# LED_Heart.net
KiCad netlist of a schematic drawn in EAGLE
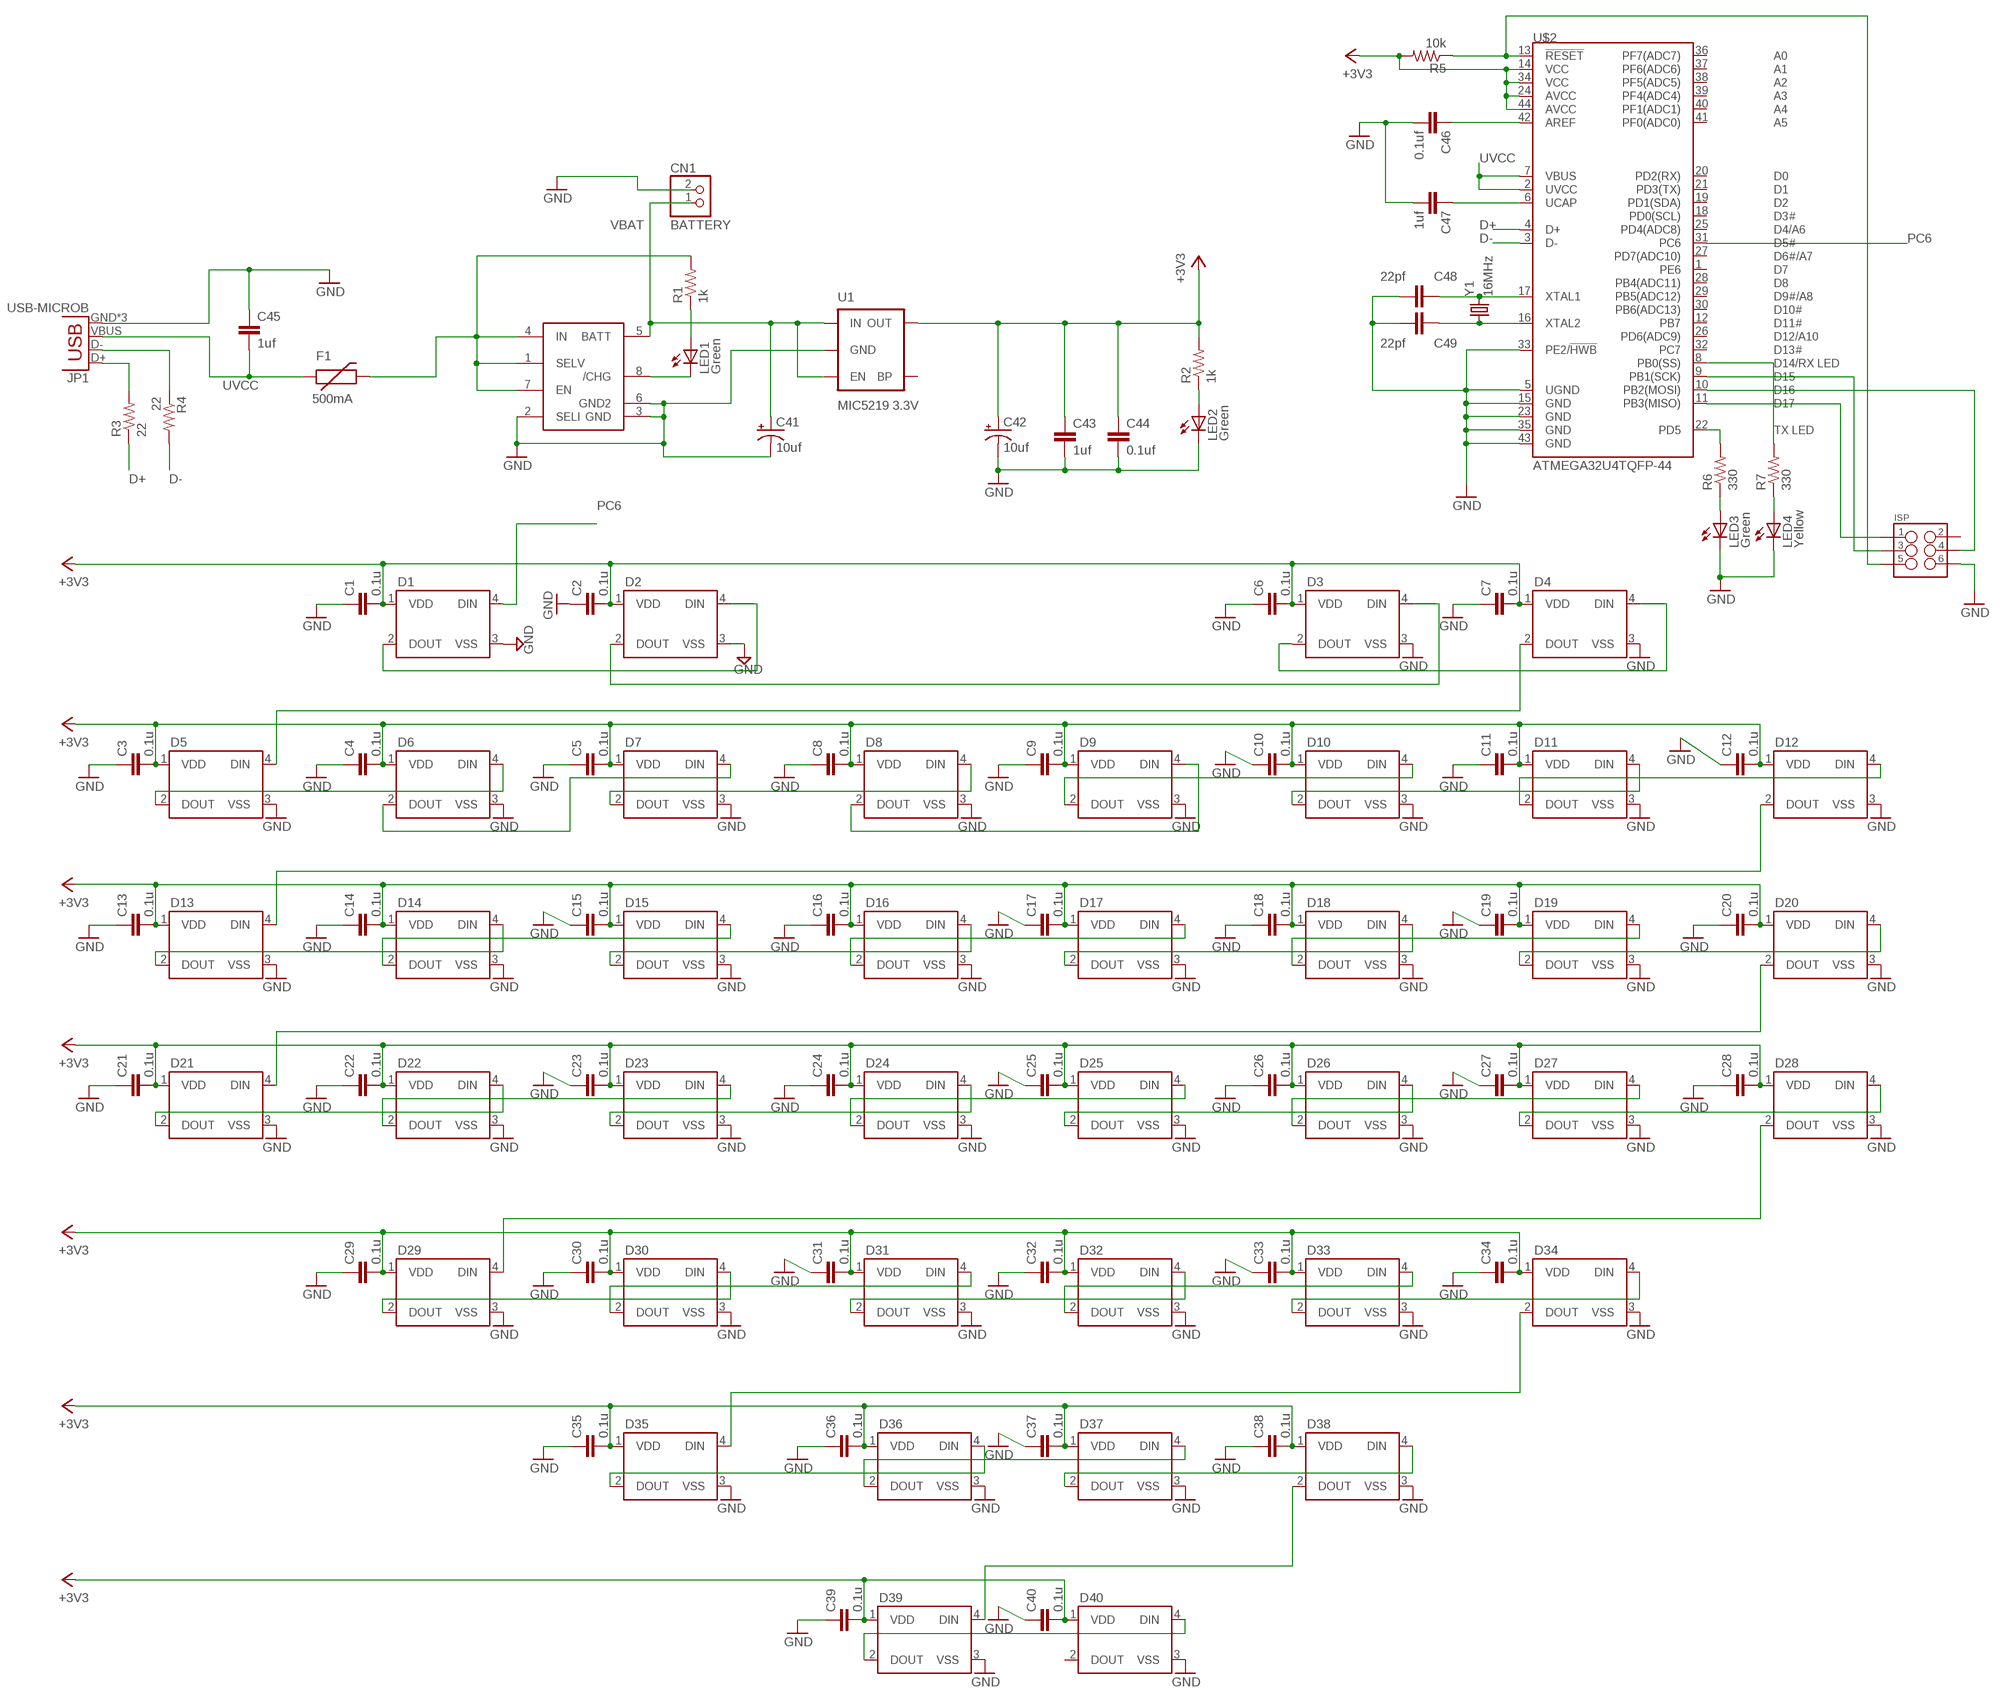
[diagram p0: schematic, sheet 1]

(export (version "E")
  (design (tool "Eeschema 10.0.6"))
  (components
    (comp (ref "C1")
      (value "0.1u")
      (footprint "eagle-import:0805")
      (libsource (lib "eagle-import") (part "CAP0805"))
    )
    (comp (ref "C2")
      (value "0.1u")
      (footprint "eagle-import:0805")
      (libsource (lib "eagle-import") (part "CAP0805"))
    )
    (comp (ref "C3")
      (value "0.1u")
      (footprint "eagle-import:0805")
      (libsource (lib "eagle-import") (part "CAP0805"))
    )
    (comp (ref "C4")
      (value "0.1u")
      (footprint "eagle-import:0805")
      (libsource (lib "eagle-import") (part "CAP0805"))
    )
    (comp (ref "C5")
      (value "0.1u")
      (footprint "eagle-import:0805")
      (libsource (lib "eagle-import") (part "CAP0805"))
    )
    (comp (ref "C6")
      (value "0.1u")
      (footprint "eagle-import:0805")
      (libsource (lib "eagle-import") (part "CAP0805"))
    )
    (comp (ref "C7")
      (value "0.1u")
      (footprint "eagle-import:0805")
      (libsource (lib "eagle-import") (part "CAP0805"))
    )
    (comp (ref "C8")
      (value "0.1u")
      (footprint "eagle-import:0805")
      (libsource (lib "eagle-import") (part "CAP0805"))
    )
    (comp (ref "C9")
      (value "0.1u")
      (footprint "eagle-import:0805")
      (libsource (lib "eagle-import") (part "CAP0805"))
    )
    (comp (ref "C10")
      (value "0.1u")
      (footprint "eagle-import:0805")
      (libsource (lib "eagle-import") (part "CAP0805"))
    )
    (comp (ref "C11")
      (value "0.1u")
      (footprint "eagle-import:0805")
      (libsource (lib "eagle-import") (part "CAP0805"))
    )
    (comp (ref "C12")
      (value "0.1u")
      (footprint "eagle-import:0805")
      (libsource (lib "eagle-import") (part "CAP0805"))
    )
    (comp (ref "C13")
      (value "0.1u")
      (footprint "eagle-import:0805")
      (libsource (lib "eagle-import") (part "CAP0805"))
    )
    (comp (ref "C14")
      (value "0.1u")
      (footprint "eagle-import:0805")
      (libsource (lib "eagle-import") (part "CAP0805"))
    )
    (comp (ref "C15")
      (value "0.1u")
      (footprint "eagle-import:0805")
      (libsource (lib "eagle-import") (part "CAP0805"))
    )
    (comp (ref "C16")
      (value "0.1u")
      (footprint "eagle-import:0805")
      (libsource (lib "eagle-import") (part "CAP0805"))
    )
    (comp (ref "C17")
      (value "0.1u")
      (footprint "eagle-import:0805")
      (libsource (lib "eagle-import") (part "CAP0805"))
    )
    (comp (ref "C18")
      (value "0.1u")
      (footprint "eagle-import:0805")
      (libsource (lib "eagle-import") (part "CAP0805"))
    )
    (comp (ref "C19")
      (value "0.1u")
      (footprint "eagle-import:0805")
      (libsource (lib "eagle-import") (part "CAP0805"))
    )
    (comp (ref "C20")
      (value "0.1u")
      (footprint "eagle-import:0805")
      (libsource (lib "eagle-import") (part "CAP0805"))
    )
    (comp (ref "C21")
      (value "0.1u")
      (footprint "eagle-import:0805")
      (libsource (lib "eagle-import") (part "CAP0805"))
    )
    (comp (ref "C22")
      (value "0.1u")
      (footprint "eagle-import:0805")
      (libsource (lib "eagle-import") (part "CAP0805"))
    )
    (comp (ref "C23")
      (value "0.1u")
      (footprint "eagle-import:0805")
      (libsource (lib "eagle-import") (part "CAP0805"))
    )
    (comp (ref "C24")
      (value "0.1u")
      (footprint "eagle-import:0805")
      (libsource (lib "eagle-import") (part "CAP0805"))
    )
    (comp (ref "C25")
      (value "0.1u")
      (footprint "eagle-import:0805")
      (libsource (lib "eagle-import") (part "CAP0805"))
    )
    (comp (ref "C26")
      (value "0.1u")
      (footprint "eagle-import:0805")
      (libsource (lib "eagle-import") (part "CAP0805"))
    )
    (comp (ref "C27")
      (value "0.1u")
      (footprint "eagle-import:0805")
      (libsource (lib "eagle-import") (part "CAP0805"))
    )
    (comp (ref "C28")
      (value "0.1u")
      (footprint "eagle-import:0805")
      (libsource (lib "eagle-import") (part "CAP0805"))
    )
    (comp (ref "C29")
      (value "0.1u")
      (footprint "eagle-import:0805")
      (libsource (lib "eagle-import") (part "CAP0805"))
    )
    (comp (ref "C30")
      (value "0.1u")
      (footprint "eagle-import:0805")
      (libsource (lib "eagle-import") (part "CAP0805"))
    )
    (comp (ref "C31")
      (value "0.1u")
      (footprint "eagle-import:0805")
      (libsource (lib "eagle-import") (part "CAP0805"))
    )
    (comp (ref "C32")
      (value "0.1u")
      (footprint "eagle-import:0805")
      (libsource (lib "eagle-import") (part "CAP0805"))
    )
    (comp (ref "C33")
      (value "0.1u")
      (footprint "eagle-import:0805")
      (libsource (lib "eagle-import") (part "CAP0805"))
    )
    (comp (ref "C34")
      (value "0.1u")
      (footprint "eagle-import:0805")
      (libsource (lib "eagle-import") (part "CAP0805"))
    )
    (comp (ref "C35")
      (value "0.1u")
      (footprint "eagle-import:0805")
      (libsource (lib "eagle-import") (part "CAP0805"))
    )
    (comp (ref "C36")
      (value "0.1u")
      (footprint "eagle-import:0805")
      (libsource (lib "eagle-import") (part "CAP0805"))
    )
    (comp (ref "C37")
      (value "0.1u")
      (footprint "eagle-import:0805")
      (libsource (lib "eagle-import") (part "CAP0805"))
    )
    (comp (ref "C38")
      (value "0.1u")
      (footprint "eagle-import:0805")
      (libsource (lib "eagle-import") (part "CAP0805"))
    )
    (comp (ref "C39")
      (value "0.1u")
      (footprint "eagle-import:0805")
      (libsource (lib "eagle-import") (part "CAP0805"))
    )
    (comp (ref "C40")
      (value "0.1u")
      (footprint "eagle-import:0805")
      (libsource (lib "eagle-import") (part "CAP0805"))
    )
    (comp (ref "C41")
      (value "10uf")
      (footprint "eagle-import:EIA3216")
      (libsource (lib "eagle-import") (part "CAP_POL1206"))
    )
    (comp (ref "C42")
      (value "10uf")
      (footprint "eagle-import:EIA3216")
      (libsource (lib "eagle-import") (part "CAP_POL1206"))
    )
    (comp (ref "C43")
      (value "1uf")
      (footprint "eagle-import:0805")
      (libsource (lib "eagle-import") (part "CAP0805"))
    )
    (comp (ref "C44")
      (value "0.1uf")
      (footprint "eagle-import:0805")
      (libsource (lib "eagle-import") (part "CAP0805"))
    )
    (comp (ref "C45")
      (value "1uf")
      (footprint "eagle-import:0805")
      (libsource (lib "eagle-import") (part "CAP0805"))
    )
    (comp (ref "C46")
      (value "0.1uf")
      (footprint "eagle-import:0805")
      (libsource (lib "eagle-import") (part "CAP0805"))
    )
    (comp (ref "C47")
      (value "1uf")
      (footprint "eagle-import:0805")
      (libsource (lib "eagle-import") (part "CAP0805"))
    )
    (comp (ref "C48")
      (value "22pf")
      (footprint "eagle-import:0805")
      (libsource (lib "eagle-import") (part "CAP0805"))
    )
    (comp (ref "C49")
      (value "22pf")
      (footprint "eagle-import:0805")
      (libsource (lib "eagle-import") (part "CAP0805"))
    )
    (comp (ref "CN1")
      (value "BATTERY")
      (footprint "eagle-import:JST-PH-2-SMT")
      (libsource (lib "eagle-import") (part "JST_2PIN-SMT"))
    )
    (comp (ref "D1")
      (value "WS2812B")
      (footprint "eagle-import:WS2812B")
      (libsource (lib "eagle-import") (part "WS2812B"))
    )
    (comp (ref "D2")
      (value "WS2812B")
      (footprint "eagle-import:WS2812B")
      (libsource (lib "eagle-import") (part "WS2812B"))
    )
    (comp (ref "D3")
      (value "WS2812B")
      (footprint "eagle-import:WS2812B")
      (libsource (lib "eagle-import") (part "WS2812B"))
    )
    (comp (ref "D4")
      (value "WS2812B")
      (footprint "eagle-import:WS2812B")
      (libsource (lib "eagle-import") (part "WS2812B"))
    )
    (comp (ref "D5")
      (value "WS2812B")
      (footprint "eagle-import:WS2812B")
      (libsource (lib "eagle-import") (part "WS2812B"))
    )
    (comp (ref "D6")
      (value "WS2812B")
      (footprint "eagle-import:WS2812B")
      (libsource (lib "eagle-import") (part "WS2812B"))
    )
    (comp (ref "D7")
      (value "WS2812B")
      (footprint "eagle-import:WS2812B")
      (libsource (lib "eagle-import") (part "WS2812B"))
    )
    (comp (ref "D8")
      (value "WS2812B")
      (footprint "eagle-import:WS2812B")
      (libsource (lib "eagle-import") (part "WS2812B"))
    )
    (comp (ref "D9")
      (value "WS2812B")
      (footprint "eagle-import:WS2812B")
      (libsource (lib "eagle-import") (part "WS2812B"))
    )
    (comp (ref "D10")
      (value "WS2812B")
      (footprint "eagle-import:WS2812B")
      (libsource (lib "eagle-import") (part "WS2812B"))
    )
    (comp (ref "D11")
      (value "WS2812B")
      (footprint "eagle-import:WS2812B")
      (libsource (lib "eagle-import") (part "WS2812B"))
    )
    (comp (ref "D12")
      (value "WS2812B")
      (footprint "eagle-import:WS2812B")
      (libsource (lib "eagle-import") (part "WS2812B"))
    )
    (comp (ref "D13")
      (value "WS2812B")
      (footprint "eagle-import:WS2812B")
      (libsource (lib "eagle-import") (part "WS2812B"))
    )
    (comp (ref "D14")
      (value "WS2812B")
      (footprint "eagle-import:WS2812B")
      (libsource (lib "eagle-import") (part "WS2812B"))
    )
    (comp (ref "D15")
      (value "WS2812B")
      (footprint "eagle-import:WS2812B")
      (libsource (lib "eagle-import") (part "WS2812B"))
    )
    (comp (ref "D16")
      (value "WS2812B")
      (footprint "eagle-import:WS2812B")
      (libsource (lib "eagle-import") (part "WS2812B"))
    )
    (comp (ref "D17")
      (value "WS2812B")
      (footprint "eagle-import:WS2812B")
      (libsource (lib "eagle-import") (part "WS2812B"))
    )
    (comp (ref "D18")
      (value "WS2812B")
      (footprint "eagle-import:WS2812B")
      (libsource (lib "eagle-import") (part "WS2812B"))
    )
    (comp (ref "D19")
      (value "WS2812B")
      (footprint "eagle-import:WS2812B")
      (libsource (lib "eagle-import") (part "WS2812B"))
    )
    (comp (ref "D20")
      (value "WS2812B")
      (footprint "eagle-import:WS2812B")
      (libsource (lib "eagle-import") (part "WS2812B"))
    )
    (comp (ref "D21")
      (value "WS2812B")
      (footprint "eagle-import:WS2812B")
      (libsource (lib "eagle-import") (part "WS2812B"))
    )
    (comp (ref "D22")
      (value "WS2812B")
      (footprint "eagle-import:WS2812B")
      (libsource (lib "eagle-import") (part "WS2812B"))
    )
    (comp (ref "D23")
      (value "WS2812B")
      (footprint "eagle-import:WS2812B")
      (libsource (lib "eagle-import") (part "WS2812B"))
    )
    (comp (ref "D24")
      (value "WS2812B")
      (footprint "eagle-import:WS2812B")
      (libsource (lib "eagle-import") (part "WS2812B"))
    )
    (comp (ref "D25")
      (value "WS2812B")
      (footprint "eagle-import:WS2812B")
      (libsource (lib "eagle-import") (part "WS2812B"))
    )
    (comp (ref "D26")
      (value "WS2812B")
      (footprint "eagle-import:WS2812B")
      (libsource (lib "eagle-import") (part "WS2812B"))
    )
    (comp (ref "D27")
      (value "WS2812B")
      (footprint "eagle-import:WS2812B")
      (libsource (lib "eagle-import") (part "WS2812B"))
    )
    (comp (ref "D28")
      (value "WS2812B")
      (footprint "eagle-import:WS2812B")
      (libsource (lib "eagle-import") (part "WS2812B"))
    )
    (comp (ref "D29")
      (value "WS2812B")
      (footprint "eagle-import:WS2812B")
      (libsource (lib "eagle-import") (part "WS2812B"))
    )
    (comp (ref "D30")
      (value "WS2812B")
      (footprint "eagle-import:WS2812B")
      (libsource (lib "eagle-import") (part "WS2812B"))
    )
    (comp (ref "D31")
      (value "WS2812B")
      (footprint "eagle-import:WS2812B")
      (libsource (lib "eagle-import") (part "WS2812B"))
    )
    (comp (ref "D32")
      (value "WS2812B")
      (footprint "eagle-import:WS2812B")
      (libsource (lib "eagle-import") (part "WS2812B"))
    )
    (comp (ref "D33")
      (value "WS2812B")
      (footprint "eagle-import:WS2812B")
      (libsource (lib "eagle-import") (part "WS2812B"))
    )
    (comp (ref "D34")
      (value "WS2812B")
      (footprint "eagle-import:WS2812B")
      (libsource (lib "eagle-import") (part "WS2812B"))
    )
    (comp (ref "D35")
      (value "WS2812B")
      (footprint "eagle-import:WS2812B")
      (libsource (lib "eagle-import") (part "WS2812B"))
    )
    (comp (ref "D36")
      (value "WS2812B")
      (footprint "eagle-import:WS2812B")
      (libsource (lib "eagle-import") (part "WS2812B"))
    )
    (comp (ref "D37")
      (value "WS2812B")
      (footprint "eagle-import:WS2812B")
      (libsource (lib "eagle-import") (part "WS2812B"))
    )
    (comp (ref "D38")
      (value "WS2812B")
      (footprint "eagle-import:WS2812B")
      (libsource (lib "eagle-import") (part "WS2812B"))
    )
    (comp (ref "D39")
      (value "WS2812B")
      (footprint "eagle-import:WS2812B")
      (libsource (lib "eagle-import") (part "WS2812B"))
    )
    (comp (ref "D40")
      (value "WS2812B")
      (footprint "eagle-import:WS2812B")
      (libsource (lib "eagle-import") (part "WS2812B"))
    )
    (comp (ref "F1")
      (value "500mA")
      (footprint "eagle-import:PTC-1206")
      (libsource (lib "eagle-import") (part "PTCSMD"))
    )
    (comp (ref "ISP")
      (value "M03X2POGO_PINS")
      (footprint "eagle-import:2X3_POGO")
      (libsource (lib "eagle-import") (part "M03X2POGO_PINS"))
    )
    (comp (ref "JP1")
      (value "USB-MICROB")
      (footprint "eagle-import:USB-MICROB")
      (libsource (lib "eagle-import") (part "USB-MICROB"))
    )
    (comp (ref "LED1")
      (value "Green")
      (footprint "eagle-import:CHIP-LED0805")
      (libsource (lib "eagle-import") (part "LEDCHIP-LED0805"))
    )
    (comp (ref "LED2")
      (value "Green")
      (footprint "eagle-import:CHIP-LED0805")
      (libsource (lib "eagle-import") (part "LEDCHIP-LED0805"))
    )
    (comp (ref "LED3")
      (value "Green")
      (footprint "eagle-import:CHIP-LED0805")
      (libsource (lib "eagle-import") (part "LEDCHIP-LED0805"))
    )
    (comp (ref "LED4")
      (value "Yellow")
      (footprint "eagle-import:CHIP-LED0805")
      (libsource (lib "eagle-import") (part "LEDCHIP-LED0805"))
    )
    (comp (ref "R1")
      (value "1k")
      (footprint "eagle-import:0805")
      (libsource (lib "eagle-import") (part "RESISTOR0805-RES"))
    )
    (comp (ref "R2")
      (value "1k")
      (footprint "eagle-import:0805")
      (libsource (lib "eagle-import") (part "RESISTOR0805-RES"))
    )
    (comp (ref "R3")
      (value "22")
      (footprint "eagle-import:0805")
      (libsource (lib "eagle-import") (part "RESISTOR0805-RES"))
    )
    (comp (ref "R4")
      (value "22")
      (footprint "eagle-import:0805")
      (libsource (lib "eagle-import") (part "RESISTOR0805-RES"))
    )
    (comp (ref "R5")
      (value "10k")
      (footprint "eagle-import:0805")
      (libsource (lib "eagle-import") (part "RESISTOR0805-RES"))
    )
    (comp (ref "R6")
      (value "330")
      (footprint "eagle-import:0805")
      (libsource (lib "eagle-import") (part "RESISTOR0805-RES"))
    )
    (comp (ref "R7")
      (value "330")
      (footprint "eagle-import:0805")
      (libsource (lib "eagle-import") (part "RESISTOR0805-RES"))
    )
    (comp (ref "U$1")
      (value "MAX1811SO8")
      (footprint "eagle-import:SO08")
      (libsource (lib "eagle-import") (part "MAX1811SO8"))
    )
    (comp (ref "U$2")
      (value "ATMEGA32U4TQFP-44")
      (footprint "eagle-import:TQFP44")
      (libsource (lib "eagle-import") (part "ATMEGA32U4TQFP-44"))
    )
    (comp (ref "U1")
      (value "MIC5219 3.3V")
      (footprint "eagle-import:SOT23-5")
      (libsource (lib "eagle-import") (part "V_REG_MIC52193.3V"))
    )
    (comp (ref "Y1")
      (value "16MHz")
      (footprint "eagle-import:CRYSTAL7X5")
      (libsource (lib "eagle-import") (part "CRYSTAL7X57X5"))
    )
  )
  (nets
    (net (code "1") (name "+3V3") (class "Default")
      (node (ref "C1") (pin "2") (pinfunction "2_2") (pintype "passive"))
      (node (ref "C10") (pin "2") (pinfunction "2_2") (pintype "passive"))
      (node (ref "C11") (pin "2") (pinfunction "2_2") (pintype "passive"))
      (node (ref "C12") (pin "2") (pinfunction "2_2") (pintype "passive"))
      (node (ref "C13") (pin "2") (pinfunction "2_2") (pintype "passive"))
      (node (ref "C14") (pin "2") (pinfunction "2_2") (pintype "passive"))
      (node (ref "C15") (pin "2") (pinfunction "2_2") (pintype "passive"))
      (node (ref "C16") (pin "2") (pinfunction "2_2") (pintype "passive"))
      (node (ref "C17") (pin "2") (pinfunction "2_2") (pintype "passive"))
      (node (ref "C18") (pin "2") (pinfunction "2_2") (pintype "passive"))
      (node (ref "C19") (pin "2") (pinfunction "2_2") (pintype "passive"))
      (node (ref "C2") (pin "2") (pinfunction "2_2") (pintype "passive"))
      (node (ref "C20") (pin "2") (pinfunction "2_2") (pintype "passive"))
      (node (ref "C21") (pin "2") (pinfunction "2_2") (pintype "passive"))
      (node (ref "C22") (pin "2") (pinfunction "2_2") (pintype "passive"))
      (node (ref "C23") (pin "2") (pinfunction "2_2") (pintype "passive"))
      (node (ref "C24") (pin "2") (pinfunction "2_2") (pintype "passive"))
      (node (ref "C25") (pin "2") (pinfunction "2_2") (pintype "passive"))
      (node (ref "C26") (pin "2") (pinfunction "2_2") (pintype "passive"))
      (node (ref "C27") (pin "2") (pinfunction "2_2") (pintype "passive"))
      (node (ref "C28") (pin "2") (pinfunction "2_2") (pintype "passive"))
      (node (ref "C29") (pin "2") (pinfunction "2_2") (pintype "passive"))
      (node (ref "C3") (pin "2") (pinfunction "2_2") (pintype "passive"))
      (node (ref "C30") (pin "2") (pinfunction "2_2") (pintype "passive"))
      (node (ref "C31") (pin "2") (pinfunction "2_2") (pintype "passive"))
      (node (ref "C32") (pin "2") (pinfunction "2_2") (pintype "passive"))
      (node (ref "C33") (pin "2") (pinfunction "2_2") (pintype "passive"))
      (node (ref "C34") (pin "2") (pinfunction "2_2") (pintype "passive"))
      (node (ref "C35") (pin "2") (pinfunction "2_2") (pintype "passive"))
      (node (ref "C36") (pin "2") (pinfunction "2_2") (pintype "passive"))
      (node (ref "C37") (pin "2") (pinfunction "2_2") (pintype "passive"))
      (node (ref "C38") (pin "2") (pinfunction "2_2") (pintype "passive"))
      (node (ref "C39") (pin "2") (pinfunction "2_2") (pintype "passive"))
      (node (ref "C4") (pin "2") (pinfunction "2_2") (pintype "passive"))
      (node (ref "C40") (pin "2") (pinfunction "2_2") (pintype "passive"))
      (node (ref "C42") (pin "A") (pinfunction "+_A") (pintype "passive"))
      (node (ref "C43") (pin "1") (pinfunction "1_1") (pintype "passive"))
      (node (ref "C44") (pin "1") (pinfunction "1_1") (pintype "passive"))
      (node (ref "C5") (pin "2") (pinfunction "2_2") (pintype "passive"))
      (node (ref "C6") (pin "2") (pinfunction "2_2") (pintype "passive"))
      (node (ref "C7") (pin "2") (pinfunction "2_2") (pintype "passive"))
      (node (ref "C8") (pin "2") (pinfunction "2_2") (pintype "passive"))
      (node (ref "C9") (pin "2") (pinfunction "2_2") (pintype "passive"))
      (node (ref "D1") (pin "1") (pinfunction "VDD_1") (pintype "power_in"))
      (node (ref "D10") (pin "1") (pinfunction "VDD_1") (pintype "power_in"))
      (node (ref "D11") (pin "1") (pinfunction "VDD_1") (pintype "power_in"))
      (node (ref "D12") (pin "1") (pinfunction "VDD_1") (pintype "power_in"))
      (node (ref "D13") (pin "1") (pinfunction "VDD_1") (pintype "power_in"))
      (node (ref "D14") (pin "1") (pinfunction "VDD_1") (pintype "power_in"))
      (node (ref "D15") (pin "1") (pinfunction "VDD_1") (pintype "power_in"))
      (node (ref "D16") (pin "1") (pinfunction "VDD_1") (pintype "power_in"))
      (node (ref "D17") (pin "1") (pinfunction "VDD_1") (pintype "power_in"))
      (node (ref "D18") (pin "1") (pinfunction "VDD_1") (pintype "power_in"))
      (node (ref "D19") (pin "1") (pinfunction "VDD_1") (pintype "power_in"))
      (node (ref "D2") (pin "1") (pinfunction "VDD_1") (pintype "power_in"))
      (node (ref "D20") (pin "1") (pinfunction "VDD_1") (pintype "power_in"))
      (node (ref "D21") (pin "1") (pinfunction "VDD_1") (pintype "power_in"))
      (node (ref "D22") (pin "1") (pinfunction "VDD_1") (pintype "power_in"))
      (node (ref "D23") (pin "1") (pinfunction "VDD_1") (pintype "power_in"))
      (node (ref "D24") (pin "1") (pinfunction "VDD_1") (pintype "power_in"))
      (node (ref "D25") (pin "1") (pinfunction "VDD_1") (pintype "power_in"))
      (node (ref "D26") (pin "1") (pinfunction "VDD_1") (pintype "power_in"))
      (node (ref "D27") (pin "1") (pinfunction "VDD_1") (pintype "power_in"))
      (node (ref "D28") (pin "1") (pinfunction "VDD_1") (pintype "power_in"))
      (node (ref "D29") (pin "1") (pinfunction "VDD_1") (pintype "power_in"))
      (node (ref "D3") (pin "1") (pinfunction "VDD_1") (pintype "power_in"))
      (node (ref "D30") (pin "1") (pinfunction "VDD_1") (pintype "power_in"))
      (node (ref "D31") (pin "1") (pinfunction "VDD_1") (pintype "power_in"))
      (node (ref "D32") (pin "1") (pinfunction "VDD_1") (pintype "power_in"))
      (node (ref "D33") (pin "1") (pinfunction "VDD_1") (pintype "power_in"))
      (node (ref "D34") (pin "1") (pinfunction "VDD_1") (pintype "power_in"))
      (node (ref "D35") (pin "1") (pinfunction "VDD_1") (pintype "power_in"))
      (node (ref "D36") (pin "1") (pinfunction "VDD_1") (pintype "power_in"))
      (node (ref "D37") (pin "1") (pinfunction "VDD_1") (pintype "power_in"))
      (node (ref "D38") (pin "1") (pinfunction "VDD_1") (pintype "power_in"))
      (node (ref "D39") (pin "1") (pinfunction "VDD_1") (pintype "power_in"))
      (node (ref "D4") (pin "1") (pinfunction "VDD_1") (pintype "power_in"))
      (node (ref "D40") (pin "1") (pinfunction "VDD_1") (pintype "power_in"))
      (node (ref "D5") (pin "1") (pinfunction "VDD_1") (pintype "power_in"))
      (node (ref "D6") (pin "1") (pinfunction "VDD_1") (pintype "power_in"))
      (node (ref "D7") (pin "1") (pinfunction "VDD_1") (pintype "power_in"))
      (node (ref "D8") (pin "1") (pinfunction "VDD_1") (pintype "power_in"))
      (node (ref "D9") (pin "1") (pinfunction "VDD_1") (pintype "power_in"))
      (node (ref "R2") (pin "2") (pinfunction "2_2") (pintype "passive"))
      (node (ref "R5") (pin "2") (pinfunction "2_2") (pintype "passive"))
      (node (ref "U$2") (pin "14") (pinfunction "VCC_14") (pintype "bidirectional"))
      (node (ref "U$2") (pin "24") (pinfunction "AVCC_24") (pintype "bidirectional"))
      (node (ref "U$2") (pin "34") (pinfunction "VCC_34") (pintype "bidirectional"))
      (node (ref "U$2") (pin "44") (pinfunction "AVCC_44") (pintype "bidirectional"))
      (node (ref "U1") (pin "5") (pinfunction "OUT_5") (pintype "passive"))
    )
    (net (code "2") (name "D+") (class "Default")
      (node (ref "R3") (pin "1") (pinfunction "1_1") (pintype "passive"))
      (node (ref "U$2") (pin "4") (pinfunction "D+_4") (pintype "bidirectional"))
    )
    (net (code "3") (name "D-") (class "Default")
      (node (ref "R4") (pin "2") (pinfunction "2_2") (pintype "passive"))
      (node (ref "U$2") (pin "3") (pinfunction "D-_3") (pintype "bidirectional"))
    )
    (net (code "4") (name "GND") (class "Default")
      (node (ref "C1") (pin "1") (pinfunction "1_1") (pintype "passive"))
      (node (ref "C10") (pin "1") (pinfunction "1_1") (pintype "passive"))
      (node (ref "C11") (pin "1") (pinfunction "1_1") (pintype "passive"))
      (node (ref "C12") (pin "1") (pinfunction "1_1") (pintype "passive"))
      (node (ref "C13") (pin "1") (pinfunction "1_1") (pintype "passive"))
      (node (ref "C14") (pin "1") (pinfunction "1_1") (pintype "passive"))
      (node (ref "C15") (pin "1") (pinfunction "1_1") (pintype "passive"))
      (node (ref "C16") (pin "1") (pinfunction "1_1") (pintype "passive"))
      (node (ref "C17") (pin "1") (pinfunction "1_1") (pintype "passive"))
      (node (ref "C18") (pin "1") (pinfunction "1_1") (pintype "passive"))
      (node (ref "C19") (pin "1") (pinfunction "1_1") (pintype "passive"))
      (node (ref "C2") (pin "1") (pinfunction "1_1") (pintype "passive"))
      (node (ref "C20") (pin "1") (pinfunction "1_1") (pintype "passive"))
      (node (ref "C21") (pin "1") (pinfunction "1_1") (pintype "passive"))
      (node (ref "C22") (pin "1") (pinfunction "1_1") (pintype "passive"))
      (node (ref "C23") (pin "1") (pinfunction "1_1") (pintype "passive"))
      (node (ref "C24") (pin "1") (pinfunction "1_1") (pintype "passive"))
      (node (ref "C25") (pin "1") (pinfunction "1_1") (pintype "passive"))
      (node (ref "C26") (pin "1") (pinfunction "1_1") (pintype "passive"))
      (node (ref "C27") (pin "1") (pinfunction "1_1") (pintype "passive"))
      (node (ref "C28") (pin "1") (pinfunction "1_1") (pintype "passive"))
      (node (ref "C29") (pin "1") (pinfunction "1_1") (pintype "passive"))
      (node (ref "C3") (pin "1") (pinfunction "1_1") (pintype "passive"))
      (node (ref "C30") (pin "1") (pinfunction "1_1") (pintype "passive"))
      (node (ref "C31") (pin "1") (pinfunction "1_1") (pintype "passive"))
      (node (ref "C32") (pin "1") (pinfunction "1_1") (pintype "passive"))
      (node (ref "C33") (pin "1") (pinfunction "1_1") (pintype "passive"))
      (node (ref "C34") (pin "1") (pinfunction "1_1") (pintype "passive"))
      (node (ref "C35") (pin "1") (pinfunction "1_1") (pintype "passive"))
      (node (ref "C36") (pin "1") (pinfunction "1_1") (pintype "passive"))
      (node (ref "C37") (pin "1") (pinfunction "1_1") (pintype "passive"))
      (node (ref "C38") (pin "1") (pinfunction "1_1") (pintype "passive"))
      (node (ref "C39") (pin "1") (pinfunction "1_1") (pintype "passive"))
      (node (ref "C4") (pin "1") (pinfunction "1_1") (pintype "passive"))
      (node (ref "C40") (pin "1") (pinfunction "1_1") (pintype "passive"))
      (node (ref "C41") (pin "C") (pinfunction "-_C") (pintype "passive"))
      (node (ref "C42") (pin "C") (pinfunction "-_C") (pintype "passive"))
      (node (ref "C43") (pin "2") (pinfunction "2_2") (pintype "passive"))
      (node (ref "C44") (pin "2") (pinfunction "2_2") (pintype "passive"))
      (node (ref "C45") (pin "1") (pinfunction "1_1") (pintype "passive"))
      (node (ref "C46") (pin "2") (pinfunction "2_2") (pintype "passive"))
      (node (ref "C47") (pin "2") (pinfunction "2_2") (pintype "passive"))
      (node (ref "C48") (pin "2") (pinfunction "2_2") (pintype "passive"))
      (node (ref "C49") (pin "2") (pinfunction "2_2") (pintype "passive"))
      (node (ref "C5") (pin "1") (pinfunction "1_1") (pintype "passive"))
      (node (ref "C6") (pin "1") (pinfunction "1_1") (pintype "passive"))
      (node (ref "C7") (pin "1") (pinfunction "1_1") (pintype "passive"))
      (node (ref "C8") (pin "1") (pinfunction "1_1") (pintype "passive"))
      (node (ref "C9") (pin "1") (pinfunction "1_1") (pintype "passive"))
      (node (ref "CN1") (pin "2") (pinfunction "1_2") (pintype "passive"))
      (node (ref "D1") (pin "3") (pinfunction "VSS_3") (pintype "power_in"))
      (node (ref "D10") (pin "3") (pinfunction "VSS_3") (pintype "power_in"))
      (node (ref "D11") (pin "3") (pinfunction "VSS_3") (pintype "power_in"))
      (node (ref "D12") (pin "3") (pinfunction "VSS_3") (pintype "power_in"))
      (node (ref "D13") (pin "3") (pinfunction "VSS_3") (pintype "power_in"))
      (node (ref "D14") (pin "3") (pinfunction "VSS_3") (pintype "power_in"))
      (node (ref "D15") (pin "3") (pinfunction "VSS_3") (pintype "power_in"))
      (node (ref "D16") (pin "3") (pinfunction "VSS_3") (pintype "power_in"))
      (node (ref "D17") (pin "3") (pinfunction "VSS_3") (pintype "power_in"))
      (node (ref "D18") (pin "3") (pinfunction "VSS_3") (pintype "power_in"))
      (node (ref "D19") (pin "3") (pinfunction "VSS_3") (pintype "power_in"))
      (node (ref "D2") (pin "3") (pinfunction "VSS_3") (pintype "power_in"))
      (node (ref "D20") (pin "3") (pinfunction "VSS_3") (pintype "power_in"))
      (node (ref "D21") (pin "3") (pinfunction "VSS_3") (pintype "power_in"))
      (node (ref "D22") (pin "3") (pinfunction "VSS_3") (pintype "power_in"))
      (node (ref "D23") (pin "3") (pinfunction "VSS_3") (pintype "power_in"))
      (node (ref "D24") (pin "3") (pinfunction "VSS_3") (pintype "power_in"))
      (node (ref "D25") (pin "3") (pinfunction "VSS_3") (pintype "power_in"))
      (node (ref "D26") (pin "3") (pinfunction "VSS_3") (pintype "power_in"))
      (node (ref "D27") (pin "3") (pinfunction "VSS_3") (pintype "power_in"))
      (node (ref "D28") (pin "3") (pinfunction "VSS_3") (pintype "power_in"))
      (node (ref "D29") (pin "3") (pinfunction "VSS_3") (pintype "power_in"))
      (node (ref "D3") (pin "3") (pinfunction "VSS_3") (pintype "power_in"))
      (node (ref "D30") (pin "3") (pinfunction "VSS_3") (pintype "power_in"))
      (node (ref "D31") (pin "3") (pinfunction "VSS_3") (pintype "power_in"))
      (node (ref "D32") (pin "3") (pinfunction "VSS_3") (pintype "power_in"))
      (node (ref "D33") (pin "3") (pinfunction "VSS_3") (pintype "power_in"))
      (node (ref "D34") (pin "3") (pinfunction "VSS_3") (pintype "power_in"))
      (node (ref "D35") (pin "3") (pinfunction "VSS_3") (pintype "power_in"))
      (node (ref "D36") (pin "3") (pinfunction "VSS_3") (pintype "power_in"))
      (node (ref "D37") (pin "3") (pinfunction "VSS_3") (pintype "power_in"))
      (node (ref "D38") (pin "3") (pinfunction "VSS_3") (pintype "power_in"))
      (node (ref "D39") (pin "3") (pinfunction "VSS_3") (pintype "power_in"))
      (node (ref "D4") (pin "3") (pinfunction "VSS_3") (pintype "power_in"))
      (node (ref "D40") (pin "3") (pinfunction "VSS_3") (pintype "power_in"))
      (node (ref "D5") (pin "3") (pinfunction "VSS_3") (pintype "power_in"))
      (node (ref "D6") (pin "3") (pinfunction "VSS_3") (pintype "power_in"))
      (node (ref "D7") (pin "3") (pinfunction "VSS_3") (pintype "power_in"))
      (node (ref "D8") (pin "3") (pinfunction "VSS_3") (pintype "power_in"))
      (node (ref "D9") (pin "3") (pinfunction "VSS_3") (pintype "power_in"))
      (node (ref "ISP") (pin "P$6") (pinfunction "6_P$6") (pintype "bidirectional"))
      (node (ref "JP1") (pin "GND") (pinfunction "GND_GND") (pintype "bidirectional"))
      (node (ref "JP1") (pin "MT1") (pinfunction "GND_MT1") (pintype "bidirectional"))
      (node (ref "JP1") (pin "MT2") (pinfunction "GND_MT2") (pintype "bidirectional"))
      (node (ref "LED2") (pin "C") (pinfunction "C_C") (pintype "passive"))
      (node (ref "LED3") (pin "C") (pinfunction "C_C") (pintype "passive"))
      (node (ref "LED4") (pin "C") (pinfunction "C_C") (pintype "passive"))
      (node (ref "U$1") (pin "2") (pinfunction "SELI_2") (pintype "bidirectional"))
      (node (ref "U$1") (pin "3") (pinfunction "GND_3") (pintype "bidirectional"))
      (node (ref "U$1") (pin "6") (pinfunction "GND2_6") (pintype "bidirectional"))
      (node (ref "U$2") (pin "15") (pinfunction "GND_15") (pintype "bidirectional"))
      (node (ref "U$2") (pin "23") (pinfunction "GND_23") (pintype "bidirectional"))
      (node (ref "U$2") (pin "33") (pinfunction "PE2/~{HWB}_33") (pintype "bidirectional"))
      (node (ref "U$2") (pin "35") (pinfunction "GND_35") (pintype "bidirectional"))
      (node (ref "U$2") (pin "43") (pinfunction "GND_43") (pintype "bidirectional"))
      (node (ref "U$2") (pin "5") (pinfunction "UGND_5") (pintype "bidirectional"))
      (node (ref "U1") (pin "2") (pinfunction "GND_2") (pintype "input"))
    )
    (net (code "5") (name "Net-(D1-DOUT)") (class "Default")
      (node (ref "D1") (pin "2") (pinfunction "DOUT_2") (pintype "output"))
      (node (ref "D2") (pin "4") (pinfunction "DIN_4") (pintype "input"))
    )
    (net (code "6") (name "Net-(D2-DOUT)") (class "Default")
      (node (ref "D2") (pin "2") (pinfunction "DOUT_2") (pintype "output"))
      (node (ref "D3") (pin "4") (pinfunction "DIN_4") (pintype "input"))
    )
    (net (code "7") (name "Net-(D3-DOUT)") (class "Default")
      (node (ref "D3") (pin "2") (pinfunction "DOUT_2") (pintype "output"))
      (node (ref "D4") (pin "4") (pinfunction "DIN_4") (pintype "input"))
    )
    (net (code "8") (name "Net-(D4-DOUT)") (class "Default")
      (node (ref "D4") (pin "2") (pinfunction "DOUT_2") (pintype "output"))
      (node (ref "D5") (pin "4") (pinfunction "DIN_4") (pintype "input"))
    )
    (net (code "9") (name "Net-(D5-DOUT)") (class "Default")
      (node (ref "D5") (pin "2") (pinfunction "DOUT_2") (pintype "output"))
      (node (ref "D6") (pin "4") (pinfunction "DIN_4") (pintype "input"))
    )
    (net (code "10") (name "Net-(D6-DOUT)") (class "Default")
      (node (ref "D6") (pin "2") (pinfunction "DOUT_2") (pintype "output"))
      (node (ref "D7") (pin "4") (pinfunction "DIN_4") (pintype "input"))
    )
    (net (code "11") (name "Net-(D7-DOUT)") (class "Default")
      (node (ref "D7") (pin "2") (pinfunction "DOUT_2") (pintype "output"))
      (node (ref "D8") (pin "4") (pinfunction "DIN_4") (pintype "input"))
    )
    (net (code "12") (name "Net-(D8-DOUT)") (class "Default")
      (node (ref "D8") (pin "2") (pinfunction "DOUT_2") (pintype "output"))
      (node (ref "D9") (pin "4") (pinfunction "DIN_4") (pintype "input"))
    )
    (net (code "13") (name "Net-(D10-DIN)") (class "Default")
      (node (ref "D10") (pin "4") (pinfunction "DIN_4") (pintype "input"))
      (node (ref "D9") (pin "2") (pinfunction "DOUT_2") (pintype "output"))
    )
    (net (code "14") (name "Net-(D10-DOUT)") (class "Default")
      (node (ref "D10") (pin "2") (pinfunction "DOUT_2") (pintype "output"))
      (node (ref "D11") (pin "4") (pinfunction "DIN_4") (pintype "input"))
    )
    (net (code "15") (name "Net-(D11-DOUT)") (class "Default")
      (node (ref "D11") (pin "2") (pinfunction "DOUT_2") (pintype "output"))
      (node (ref "D12") (pin "4") (pinfunction "DIN_4") (pintype "input"))
    )
    (net (code "16") (name "Net-(D12-DOUT)") (class "Default")
      (node (ref "D12") (pin "2") (pinfunction "DOUT_2") (pintype "output"))
      (node (ref "D13") (pin "4") (pinfunction "DIN_4") (pintype "input"))
    )
    (net (code "17") (name "Net-(D13-DOUT)") (class "Default")
      (node (ref "D13") (pin "2") (pinfunction "DOUT_2") (pintype "output"))
      (node (ref "D14") (pin "4") (pinfunction "DIN_4") (pintype "input"))
    )
    (net (code "18") (name "Net-(D14-DOUT)") (class "Default")
      (node (ref "D14") (pin "2") (pinfunction "DOUT_2") (pintype "output"))
      (node (ref "D15") (pin "4") (pinfunction "DIN_4") (pintype "input"))
    )
    (net (code "19") (name "Net-(D15-DOUT)") (class "Default")
      (node (ref "D15") (pin "2") (pinfunction "DOUT_2") (pintype "output"))
      (node (ref "D16") (pin "4") (pinfunction "DIN_4") (pintype "input"))
    )
    (net (code "20") (name "Net-(D16-DOUT)") (class "Default")
      (node (ref "D16") (pin "2") (pinfunction "DOUT_2") (pintype "output"))
      (node (ref "D17") (pin "4") (pinfunction "DIN_4") (pintype "input"))
    )
    (net (code "21") (name "Net-(D17-DOUT)") (class "Default")
      (node (ref "D17") (pin "2") (pinfunction "DOUT_2") (pintype "output"))
      (node (ref "D18") (pin "4") (pinfunction "DIN_4") (pintype "input"))
    )
    (net (code "22") (name "Net-(D18-DOUT)") (class "Default")
      (node (ref "D18") (pin "2") (pinfunction "DOUT_2") (pintype "output"))
      (node (ref "D19") (pin "4") (pinfunction "DIN_4") (pintype "input"))
    )
    (net (code "23") (name "Net-(D19-DOUT)") (class "Default")
      (node (ref "D19") (pin "2") (pinfunction "DOUT_2") (pintype "output"))
      (node (ref "D20") (pin "4") (pinfunction "DIN_4") (pintype "input"))
    )
    (net (code "24") (name "Net-(D20-DOUT)") (class "Default")
      (node (ref "D20") (pin "2") (pinfunction "DOUT_2") (pintype "output"))
      (node (ref "D21") (pin "4") (pinfunction "DIN_4") (pintype "input"))
    )
    (net (code "25") (name "Net-(D21-DOUT)") (class "Default")
      (node (ref "D21") (pin "2") (pinfunction "DOUT_2") (pintype "output"))
      (node (ref "D22") (pin "4") (pinfunction "DIN_4") (pintype "input"))
    )
    (net (code "26") (name "Net-(D22-DOUT)") (class "Default")
      (node (ref "D22") (pin "2") (pinfunction "DOUT_2") (pintype "output"))
      (node (ref "D23") (pin "4") (pinfunction "DIN_4") (pintype "input"))
    )
    (net (code "27") (name "Net-(D23-DOUT)") (class "Default")
      (node (ref "D23") (pin "2") (pinfunction "DOUT_2") (pintype "output"))
      (node (ref "D24") (pin "4") (pinfunction "DIN_4") (pintype "input"))
    )
    (net (code "28") (name "Net-(D24-DOUT)") (class "Default")
      (node (ref "D24") (pin "2") (pinfunction "DOUT_2") (pintype "output"))
      (node (ref "D25") (pin "4") (pinfunction "DIN_4") (pintype "input"))
    )
    (net (code "29") (name "Net-(D25-DOUT)") (class "Default")
      (node (ref "D25") (pin "2") (pinfunction "DOUT_2") (pintype "output"))
      (node (ref "D26") (pin "4") (pinfunction "DIN_4") (pintype "input"))
    )
    (net (code "30") (name "Net-(D26-DOUT)") (class "Default")
      (node (ref "D26") (pin "2") (pinfunction "DOUT_2") (pintype "output"))
      (node (ref "D27") (pin "4") (pinfunction "DIN_4") (pintype "input"))
    )
    (net (code "31") (name "Net-(D27-DOUT)") (class "Default")
      (node (ref "D27") (pin "2") (pinfunction "DOUT_2") (pintype "output"))
      (node (ref "D28") (pin "4") (pinfunction "DIN_4") (pintype "input"))
    )
    (net (code "32") (name "Net-(D28-DOUT)") (class "Default")
      (node (ref "D28") (pin "2") (pinfunction "DOUT_2") (pintype "output"))
      (node (ref "D29") (pin "4") (pinfunction "DIN_4") (pintype "input"))
    )
    (net (code "33") (name "Net-(D29-DOUT)") (class "Default")
      (node (ref "D29") (pin "2") (pinfunction "DOUT_2") (pintype "output"))
      (node (ref "D30") (pin "4") (pinfunction "DIN_4") (pintype "input"))
    )
    (net (code "34") (name "Net-(D30-DOUT)") (class "Default")
      (node (ref "D30") (pin "2") (pinfunction "DOUT_2") (pintype "output"))
      (node (ref "D31") (pin "4") (pinfunction "DIN_4") (pintype "input"))
    )
    (net (code "35") (name "Net-(D31-DOUT)") (class "Default")
      (node (ref "D31") (pin "2") (pinfunction "DOUT_2") (pintype "output"))
      (node (ref "D32") (pin "4") (pinfunction "DIN_4") (pintype "input"))
    )
    (net (code "36") (name "Net-(D32-DOUT)") (class "Default")
      (node (ref "D32") (pin "2") (pinfunction "DOUT_2") (pintype "output"))
      (node (ref "D33") (pin "4") (pinfunction "DIN_4") (pintype "input"))
    )
    (net (code "37") (name "Net-(D33-DOUT)") (class "Default")
      (node (ref "D33") (pin "2") (pinfunction "DOUT_2") (pintype "output"))
      (node (ref "D34") (pin "4") (pinfunction "DIN_4") (pintype "input"))
    )
    (net (code "38") (name "Net-(D34-DOUT)") (class "Default")
      (node (ref "D34") (pin "2") (pinfunction "DOUT_2") (pintype "output"))
      (node (ref "D35") (pin "4") (pinfunction "DIN_4") (pintype "input"))
    )
    (net (code "39") (name "Net-(D35-DOUT)") (class "Default")
      (node (ref "D35") (pin "2") (pinfunction "DOUT_2") (pintype "output"))
      (node (ref "D36") (pin "4") (pinfunction "DIN_4") (pintype "input"))
    )
    (net (code "40") (name "Net-(D36-DOUT)") (class "Default")
      (node (ref "D36") (pin "2") (pinfunction "DOUT_2") (pintype "output"))
      (node (ref "D37") (pin "4") (pinfunction "DIN_4") (pintype "input"))
    )
    (net (code "41") (name "Net-(D37-DOUT)") (class "Default")
      (node (ref "D37") (pin "2") (pinfunction "DOUT_2") (pintype "output"))
      (node (ref "D38") (pin "4") (pinfunction "DIN_4") (pintype "input"))
    )
    (net (code "42") (name "Net-(D38-DOUT)") (class "Default")
      (node (ref "D38") (pin "2") (pinfunction "DOUT_2") (pintype "output"))
      (node (ref "D39") (pin "4") (pinfunction "DIN_4") (pintype "input"))
    )
    (net (code "43") (name "Net-(D39-DOUT)") (class "Default")
      (node (ref "D39") (pin "2") (pinfunction "DOUT_2") (pintype "output"))
      (node (ref "D40") (pin "4") (pinfunction "DIN_4") (pintype "input"))
    )
    (net (code "44") (name "Net-(ISP-1)") (class "Default")
      (node (ref "ISP") (pin "P$1") (pinfunction "1_P$1") (pintype "bidirectional"))
      (node (ref "U$2") (pin "11") (pinfunction "PB3(MISO)_11") (pintype "bidirectional"))
    )
    (net (code "45") (name "Net-(ISP-3)") (class "Default")
      (node (ref "ISP") (pin "P$3") (pinfunction "3_P$3") (pintype "bidirectional"))
      (node (ref "U$2") (pin "9") (pinfunction "PB1(SCK)_9") (pintype "bidirectional"))
    )
    (net (code "46") (name "Net-(ISP-4)") (class "Default")
      (node (ref "ISP") (pin "P$4") (pinfunction "4_P$4") (pintype "bidirectional"))
      (node (ref "U$2") (pin "10") (pinfunction "PB2(MOSI)_10") (pintype "bidirectional"))
    )
    (net (code "47") (name "Net-(ISP-5)") (class "Default")
      (node (ref "ISP") (pin "P$5") (pinfunction "5_P$5") (pintype "bidirectional"))
      (node (ref "R5") (pin "1") (pinfunction "1_1") (pintype "passive"))
      (node (ref "U$2") (pin "13") (pinfunction "~{RESET}_13") (pintype "bidirectional"))
    )
    (net (code "48") (name "Net-(JP1-PadD+)") (class "Default")
      (node (ref "JP1") (pin "D+") (pinfunction "D+_D+") (pintype "bidirectional"))
      (node (ref "R3") (pin "2") (pinfunction "2_2") (pintype "passive"))
    )
    (net (code "49") (name "Net-(JP1-PadD-)") (class "Default")
      (node (ref "JP1") (pin "D-") (pinfunction "D-_D-") (pintype "bidirectional"))
      (node (ref "R4") (pin "1") (pinfunction "1_1") (pintype "passive"))
    )
    (net (code "50") (name "Net-(LED1-PadA)") (class "Default")
      (node (ref "LED1") (pin "A") (pinfunction "A_A") (pintype "passive"))
      (node (ref "R1") (pin "1") (pinfunction "1_1") (pintype "passive"))
    )
    (net (code "51") (name "Net-(LED2-PadA)") (class "Default")
      (node (ref "LED2") (pin "A") (pinfunction "A_A") (pintype "passive"))
      (node (ref "R2") (pin "1") (pinfunction "1_1") (pintype "passive"))
    )
    (net (code "52") (name "Net-(LED3-PadA)") (class "Default")
      (node (ref "LED3") (pin "A") (pinfunction "A_A") (pintype "passive"))
      (node (ref "R6") (pin "1") (pinfunction "1_1") (pintype "passive"))
    )
    (net (code "53") (name "Net-(LED4-PadA)") (class "Default")
      (node (ref "LED4") (pin "A") (pinfunction "A_A") (pintype "passive"))
      (node (ref "R7") (pin "1") (pinfunction "1_1") (pintype "passive"))
    )
    (net (code "54") (name "Net-(U$1-EN)") (class "Default")
      (node (ref "F1") (pin "2") (pinfunction "2_2") (pintype "bidirectional"))
      (node (ref "R1") (pin "2") (pinfunction "2_2") (pintype "passive"))
      (node (ref "U$1") (pin "1") (pinfunction "SELV_1") (pintype "bidirectional"))
      (node (ref "U$1") (pin "4") (pinfunction "IN_4") (pintype "bidirectional"))
      (node (ref "U$1") (pin "7") (pinfunction "EN_7") (pintype "bidirectional"))
    )
    (net (code "55") (name "Net-(U$1-{slash}CHG)") (class "Default")
      (node (ref "LED1") (pin "C") (pinfunction "C_C") (pintype "passive"))
      (node (ref "U$1") (pin "8") (pinfunction "/CHG_8") (pintype "bidirectional"))
    )
    (net (code "56") (name "Net-(U$2-AREF)") (class "Default")
      (node (ref "C46") (pin "1") (pinfunction "1_1") (pintype "passive"))
      (node (ref "U$2") (pin "42") (pinfunction "AREF_42") (pintype "bidirectional"))
    )
    (net (code "57") (name "Net-(U$2-PB0(SS))") (class "Default")
      (node (ref "R7") (pin "2") (pinfunction "2_2") (pintype "passive"))
      (node (ref "U$2") (pin "8") (pinfunction "PB0(SS)_8") (pintype "bidirectional"))
    )
    (net (code "58") (name "Net-(U$2-PD5)") (class "Default")
      (node (ref "R6") (pin "2") (pinfunction "2_2") (pintype "passive"))
      (node (ref "U$2") (pin "22") (pinfunction "PD5_22") (pintype "bidirectional"))
    )
    (net (code "59") (name "Net-(U$2-UCAP)") (class "Default")
      (node (ref "C47") (pin "1") (pinfunction "1_1") (pintype "passive"))
      (node (ref "U$2") (pin "6") (pinfunction "UCAP_6") (pintype "bidirectional"))
    )
    (net (code "60") (name "Net-(U$2-XTAL1)") (class "Default")
      (node (ref "C48") (pin "1") (pinfunction "1_1") (pintype "passive"))
      (node (ref "U$2") (pin "17") (pinfunction "XTAL1_17") (pintype "bidirectional"))
      (node (ref "Y1") (pin "3") (pinfunction "2_3") (pintype "passive"))
    )
    (net (code "61") (name "Net-(U$2-XTAL2)") (class "Default")
      (node (ref "C49") (pin "1") (pinfunction "1_1") (pintype "passive"))
      (node (ref "U$2") (pin "16") (pinfunction "XTAL2_16") (pintype "bidirectional"))
      (node (ref "Y1") (pin "1") (pinfunction "1_1") (pintype "passive"))
    )
    (net (code "62") (name "PC6") (class "Default")
      (node (ref "D1") (pin "4") (pinfunction "DIN_4") (pintype "input"))
      (node (ref "U$2") (pin "31") (pinfunction "PC6_31") (pintype "bidirectional"))
    )
    (net (code "63") (name "UVCC") (class "Default")
      (node (ref "C45") (pin "2") (pinfunction "2_2") (pintype "passive"))
      (node (ref "F1") (pin "1") (pinfunction "1_1") (pintype "bidirectional"))
      (node (ref "JP1") (pin "VBUS") (pinfunction "VBUS_VBUS") (pintype "bidirectional"))
      (node (ref "U$2") (pin "2") (pinfunction "UVCC_2") (pintype "bidirectional"))
      (node (ref "U$2") (pin "7") (pinfunction "VBUS_7") (pintype "bidirectional"))
    )
    (net (code "64") (name "VBAT") (class "Default")
      (node (ref "C41") (pin "A") (pinfunction "+_A") (pintype "passive"))
      (node (ref "CN1") (pin "1") (pinfunction "2_1") (pintype "passive"))
      (node (ref "U$1") (pin "5") (pinfunction "BATT_5") (pintype "bidirectional"))
      (node (ref "U1") (pin "1") (pinfunction "IN_1") (pintype "input"))
      (node (ref "U1") (pin "3") (pinfunction "EN_3") (pintype "input"))
    )
    (net (code "65") (name "unconnected-(D40-DOUT-Pad2)") (class "Default")
      (node (ref "D40") (pin "2") (pinfunction "DOUT_2") (pintype "output"))
    )
    (net (code "66") (name "unconnected-(ISP-2-PadP$2)") (class "Default")
      (node (ref "ISP") (pin "P$2") (pinfunction "2_P$2") (pintype "bidirectional"))
    )
    (net (code "67") (name "unconnected-(U$2-PB4(ADC11)-Pad28)") (class "Default")
      (node (ref "U$2") (pin "28") (pinfunction "PB4(ADC11)_28") (pintype "bidirectional"))
    )
    (net (code "68") (name "unconnected-(U$2-PB5(ADC12)-Pad29)") (class "Default")
      (node (ref "U$2") (pin "29") (pinfunction "PB5(ADC12)_29") (pintype "bidirectional"))
    )
    (net (code "69") (name "unconnected-(U$2-PB6(ADC13)-Pad30)") (class "Default")
      (node (ref "U$2") (pin "30") (pinfunction "PB6(ADC13)_30") (pintype "bidirectional"))
    )
    (net (code "70") (name "unconnected-(U$2-PB7-Pad12)") (class "Default")
      (node (ref "U$2") (pin "12") (pinfunction "PB7_12") (pintype "bidirectional"))
    )
    (net (code "71") (name "unconnected-(U$2-PC7-Pad32)") (class "Default")
      (node (ref "U$2") (pin "32") (pinfunction "PC7_32") (pintype "bidirectional"))
    )
    (net (code "72") (name "unconnected-(U$2-PD0(SCL)-Pad18)") (class "Default")
      (node (ref "U$2") (pin "18") (pinfunction "PD0(SCL)_18") (pintype "bidirectional"))
    )
    (net (code "73") (name "unconnected-(U$2-PD1(SDA)-Pad19)") (class "Default")
      (node (ref "U$2") (pin "19") (pinfunction "PD1(SDA)_19") (pintype "bidirectional"))
    )
    (net (code "74") (name "unconnected-(U$2-PD2(RX)-Pad20)") (class "Default")
      (node (ref "U$2") (pin "20") (pinfunction "PD2(RX)_20") (pintype "bidirectional"))
    )
    (net (code "75") (name "unconnected-(U$2-PD3(TX)-Pad21)") (class "Default")
      (node (ref "U$2") (pin "21") (pinfunction "PD3(TX)_21") (pintype "bidirectional"))
    )
    (net (code "76") (name "unconnected-(U$2-PD4(ADC8)-Pad25)") (class "Default")
      (node (ref "U$2") (pin "25") (pinfunction "PD4(ADC8)_25") (pintype "bidirectional"))
    )
    (net (code "77") (name "unconnected-(U$2-PD6(ADC9)-Pad26)") (class "Default")
      (node (ref "U$2") (pin "26") (pinfunction "PD6(ADC9)_26") (pintype "bidirectional"))
    )
    (net (code "78") (name "unconnected-(U$2-PD7(ADC10)-Pad27)") (class "Default")
      (node (ref "U$2") (pin "27") (pinfunction "PD7(ADC10)_27") (pintype "bidirectional"))
    )
    (net (code "79") (name "unconnected-(U$2-PE6-Pad1)") (class "Default")
      (node (ref "U$2") (pin "1") (pinfunction "PE6_1") (pintype "bidirectional"))
    )
    (net (code "80") (name "unconnected-(U$2-PF0(ADC0)-Pad41)") (class "Default")
      (node (ref "U$2") (pin "41") (pinfunction "PF0(ADC0)_41") (pintype "bidirectional"))
    )
    (net (code "81") (name "unconnected-(U$2-PF1(ADC1)-Pad40)") (class "Default")
      (node (ref "U$2") (pin "40") (pinfunction "PF1(ADC1)_40") (pintype "bidirectional"))
    )
    (net (code "82") (name "unconnected-(U$2-PF4(ADC4)-Pad39)") (class "Default")
      (node (ref "U$2") (pin "39") (pinfunction "PF4(ADC4)_39") (pintype "bidirectional"))
    )
    (net (code "83") (name "unconnected-(U$2-PF5(ADC5)-Pad38)") (class "Default")
      (node (ref "U$2") (pin "38") (pinfunction "PF5(ADC5)_38") (pintype "bidirectional"))
    )
    (net (code "84") (name "unconnected-(U$2-PF6(ADC6)-Pad37)") (class "Default")
      (node (ref "U$2") (pin "37") (pinfunction "PF6(ADC6)_37") (pintype "bidirectional"))
    )
    (net (code "85") (name "unconnected-(U$2-PF7(ADC7)-Pad36)") (class "Default")
      (node (ref "U$2") (pin "36") (pinfunction "PF7(ADC7)_36") (pintype "bidirectional"))
    )
    (net (code "86") (name "unconnected-(U1-BP-Pad4)") (class "Default")
      (node (ref "U1") (pin "4") (pinfunction "BP_4") (pintype "input"))
    )
  )
)
